# feather.net
KiCad netlist of a schematic drawn in EAGLE
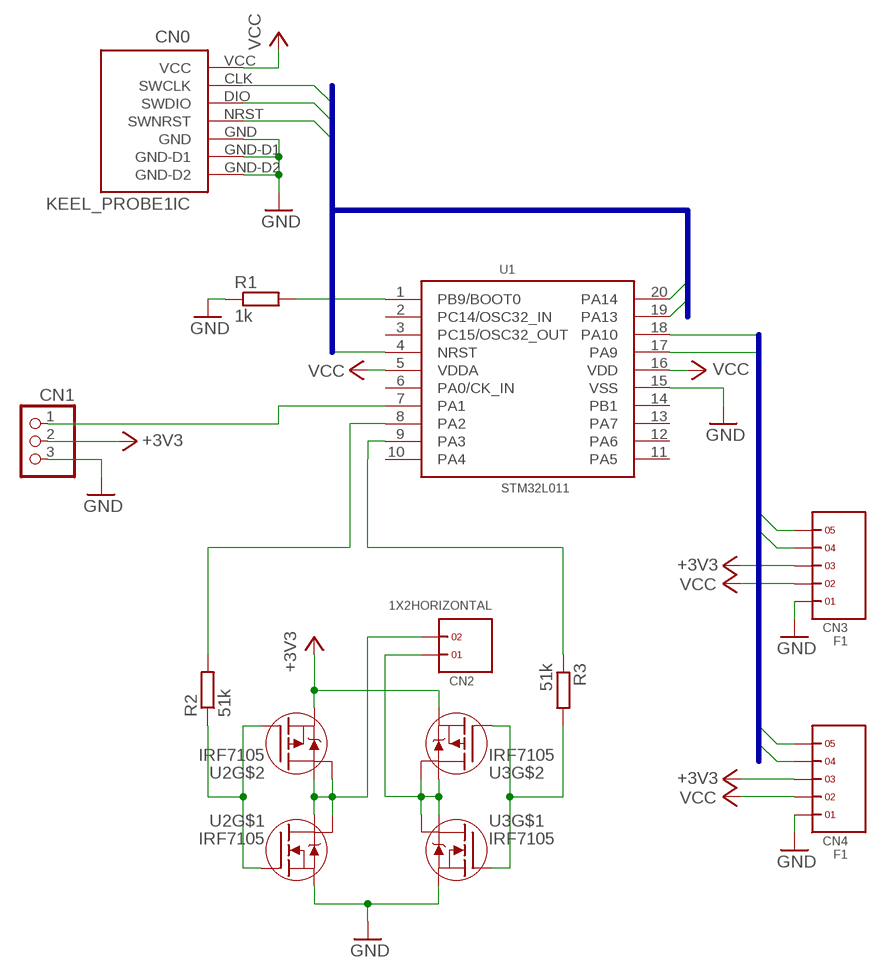
[diagram p0: schematic, sheet 1]

(export (version "E")
  (design (tool "Eeschema 10.0.6"))
  (components
    (comp (ref "CN0")
      (value "KEEL_PROBE1IC")
      (footprint "eagle-import:KEEL_PROBE-IC1")
      (libsource (lib "eagle-import") (part "KEEL_PROBE1IC"))
    )
    (comp (ref "CN1")
      (value "PINHD-1X3/90")
      (footprint "eagle-import:1X03_90")
      (libsource (lib "eagle-import") (part "PINHD-1X3/90"))
    )
    (comp (ref "CN2")
      (value "1X2HORIZONTAL")
      (footprint "eagle-import:1X2H")
      (libsource (lib "eagle-import") (part "1X2HORIZONTAL"))
    )
    (comp (ref "CN3")
      (value "F1")
      (footprint "eagle-import:1X5H")
      (libsource (lib "eagle-import") (part "1X5HORIZONTAL"))
    )
    (comp (ref "CN4")
      (value "F1")
      (footprint "eagle-import:1X5H")
      (libsource (lib "eagle-import") (part "1X5HORIZONTAL"))
    )
    (comp (ref "R1")
      (value "1k")
      (footprint "eagle-import:R0805")
      (libsource (lib "eagle-import") (part "R-EU_R0805"))
    )
    (comp (ref "R2")
      (value "51k")
      (footprint "eagle-import:R0805")
      (libsource (lib "eagle-import") (part "R-EU_R0805"))
    )
    (comp (ref "R3")
      (value "51k")
      (footprint "eagle-import:R0805")
      (libsource (lib "eagle-import") (part "R-EU_R0805"))
    )
    (comp (ref "U1")
      (value "STM32L011")
      (footprint "eagle-import:SSOP20")
      (libsource (lib "eagle-import") (part "STM32L011"))
    )
    (comp (ref "U2")
      (value "IRF7105")
      (footprint "eagle-import:SO8-2")
      (libsource (lib "eagle-import") (part "IRF7105"))
    )
    (comp (ref "U3")
      (value "IRF7105")
      (footprint "eagle-import:SO8-2")
      (libsource (lib "eagle-import") (part "IRF7105"))
    )
  )
  (nets
    (net (code "1") (name "+3V3") (class "Default")
      (node (ref "CN1") (pin "2") (pinfunction "2_2") (pintype "passive"))
      (node (ref "CN3") (pin "3") (pinfunction "3_3") (pintype "bidirectional"))
      (node (ref "CN4") (pin "3") (pinfunction "3_3") (pintype "bidirectional"))
      (node (ref "U2") (pin "3") (pinfunction "S_3") (pintype "bidirectional"))
      (node (ref "U3") (pin "3") (pinfunction "S_3") (pintype "bidirectional"))
    )
    (net (code "2") (name "/I2C_SCL") (class "Default")
      (node (ref "CN3") (pin "4") (pinfunction "4_4") (pintype "bidirectional"))
      (node (ref "CN4") (pin "4") (pinfunction "4_4") (pintype "bidirectional"))
      (node (ref "U1") (pin "17") (pinfunction "PA9_17") (pintype "bidirectional"))
    )
    (net (code "3") (name "/I2C_SDA") (class "Default")
      (node (ref "CN3") (pin "5") (pinfunction "5_5") (pintype "bidirectional"))
      (node (ref "CN4") (pin "5") (pinfunction "5_5") (pintype "bidirectional"))
      (node (ref "U1") (pin "18") (pinfunction "PA10_18") (pintype "bidirectional"))
    )
    (net (code "4") (name "/NRST") (class "Default")
      (node (ref "CN0") (pin "NRST") (pinfunction "SWNRST_NRST") (pintype "bidirectional"))
      (node (ref "U1") (pin "4") (pinfunction "NRST_4") (pintype "bidirectional"))
    )
    (net (code "5") (name "/SWCLK") (class "Default")
      (node (ref "CN0") (pin "CLK") (pinfunction "SWCLK_CLK") (pintype "bidirectional"))
      (node (ref "U1") (pin "20") (pinfunction "PA14_20") (pintype "bidirectional"))
    )
    (net (code "6") (name "/SWDIO") (class "Default")
      (node (ref "CN0") (pin "DIO") (pinfunction "SWDIO_DIO") (pintype "bidirectional"))
      (node (ref "U1") (pin "19") (pinfunction "PA13_19") (pintype "bidirectional"))
    )
    (net (code "7") (name "GND") (class "Default")
      (node (ref "CN0") (pin "GND") (pinfunction "GND_GND") (pintype "power_in"))
      (node (ref "CN0") (pin "GND-D1") (pinfunction "GND-D1_GND-D1") (pintype "power_in"))
      (node (ref "CN0") (pin "GND-D2") (pinfunction "GND-D2_GND-D2") (pintype "power_in"))
      (node (ref "CN1") (pin "3") (pinfunction "3_3") (pintype "passive"))
      (node (ref "CN3") (pin "1") (pinfunction "1_1") (pintype "bidirectional"))
      (node (ref "CN4") (pin "1") (pinfunction "1_1") (pintype "bidirectional"))
      (node (ref "R1") (pin "1") (pinfunction "1_1") (pintype "passive"))
      (node (ref "U1") (pin "15") (pinfunction "VSS_15") (pintype "power_in"))
      (node (ref "U2") (pin "1") (pinfunction "S_1") (pintype "bidirectional"))
      (node (ref "U3") (pin "1") (pinfunction "S_1") (pintype "bidirectional"))
    )
    (net (code "8") (name "Net-(CN2-Pad1)") (class "Default")
      (node (ref "CN2") (pin "1") (pinfunction "1_1") (pintype "bidirectional"))
      (node (ref "U3") (pin "5") (pinfunction "D_5") (pintype "bidirectional"))
      (node (ref "U3") (pin "6") (pinfunction "D_6") (pintype "bidirectional"))
      (node (ref "U3") (pin "7") (pinfunction "D_7") (pintype "bidirectional"))
      (node (ref "U3") (pin "8") (pinfunction "D_8") (pintype "bidirectional"))
    )
    (net (code "9") (name "Net-(CN2-Pad2)") (class "Default")
      (node (ref "CN2") (pin "2") (pinfunction "2_2") (pintype "bidirectional"))
      (node (ref "U2") (pin "5") (pinfunction "D_5") (pintype "bidirectional"))
      (node (ref "U2") (pin "6") (pinfunction "D_6") (pintype "bidirectional"))
      (node (ref "U2") (pin "7") (pinfunction "D_7") (pintype "bidirectional"))
      (node (ref "U2") (pin "8") (pinfunction "D_8") (pintype "bidirectional"))
    )
    (net (code "10") (name "Net-(U1-PA1)") (class "Default")
      (node (ref "CN1") (pin "1") (pinfunction "1_1") (pintype "passive"))
      (node (ref "U1") (pin "7") (pinfunction "PA1_7") (pintype "bidirectional"))
    )
    (net (code "11") (name "Net-(U1-PA2)") (class "Default")
      (node (ref "R2") (pin "2") (pinfunction "2_2") (pintype "passive"))
      (node (ref "U1") (pin "8") (pinfunction "PA2_8") (pintype "bidirectional"))
    )
    (net (code "12") (name "Net-(U1-PA3)") (class "Default")
      (node (ref "R3") (pin "1") (pinfunction "1_1") (pintype "passive"))
      (node (ref "U1") (pin "9") (pinfunction "PA3_9") (pintype "bidirectional"))
    )
    (net (code "13") (name "Net-(U1-PB9{slash}BOOT0)") (class "Default")
      (node (ref "R1") (pin "2") (pinfunction "2_2") (pintype "passive"))
      (node (ref "U1") (pin "1") (pinfunction "PB9/BOOT0_1") (pintype "bidirectional"))
    )
    (net (code "14") (name "Net-(U2A-G)") (class "Default")
      (node (ref "R2") (pin "1") (pinfunction "1_1") (pintype "passive"))
      (node (ref "U2") (pin "2") (pinfunction "G_2") (pintype "bidirectional"))
      (node (ref "U2") (pin "4") (pinfunction "G_4") (pintype "bidirectional"))
    )
    (net (code "15") (name "Net-(U3A-G)") (class "Default")
      (node (ref "R3") (pin "2") (pinfunction "2_2") (pintype "passive"))
      (node (ref "U3") (pin "2") (pinfunction "G_2") (pintype "bidirectional"))
      (node (ref "U3") (pin "4") (pinfunction "G_4") (pintype "bidirectional"))
    )
    (net (code "16") (name "VCC") (class "Default")
      (node (ref "CN0") (pin "VCC") (pinfunction "VCC_VCC") (pintype "power_in"))
      (node (ref "CN3") (pin "2") (pinfunction "2_2") (pintype "bidirectional"))
      (node (ref "CN4") (pin "2") (pinfunction "2_2") (pintype "bidirectional"))
      (node (ref "U1") (pin "16") (pinfunction "VDD_16") (pintype "power_in"))
      (node (ref "U1") (pin "5") (pinfunction "VDDA_5") (pintype "power_in"))
    )
    (net (code "17") (name "unconnected-(U1-PA0{slash}CK_IN-Pad6)") (class "Default")
      (node (ref "U1") (pin "6") (pinfunction "PA0/CK_IN_6") (pintype "bidirectional"))
    )
    (net (code "18") (name "unconnected-(U1-PA4-Pad10)") (class "Default")
      (node (ref "U1") (pin "10") (pinfunction "PA4_10") (pintype "bidirectional"))
    )
    (net (code "19") (name "unconnected-(U1-PA5-Pad11)") (class "Default")
      (node (ref "U1") (pin "11") (pinfunction "PA5_11") (pintype "bidirectional"))
    )
    (net (code "20") (name "unconnected-(U1-PA6-Pad12)") (class "Default")
      (node (ref "U1") (pin "12") (pinfunction "PA6_12") (pintype "bidirectional"))
    )
    (net (code "21") (name "unconnected-(U1-PA7-Pad13)") (class "Default")
      (node (ref "U1") (pin "13") (pinfunction "PA7_13") (pintype "bidirectional"))
    )
    (net (code "22") (name "unconnected-(U1-PB1-Pad14)") (class "Default")
      (node (ref "U1") (pin "14") (pinfunction "PB1_14") (pintype "bidirectional"))
    )
    (net (code "23") (name "unconnected-(U1-PC14{slash}OSC32_IN-Pad2)") (class "Default")
      (node (ref "U1") (pin "2") (pinfunction "PC14/OSC32_IN_2") (pintype "bidirectional"))
    )
    (net (code "24") (name "unconnected-(U1-PC15{slash}OSC32_OUT-Pad3)") (class "Default")
      (node (ref "U1") (pin "3") (pinfunction "PC15/OSC32_OUT_3") (pintype "bidirectional"))
    )
  )
)
